# MODULIQ_CFD.net
KiCad netlist of a schematic drawn in Altium Designer
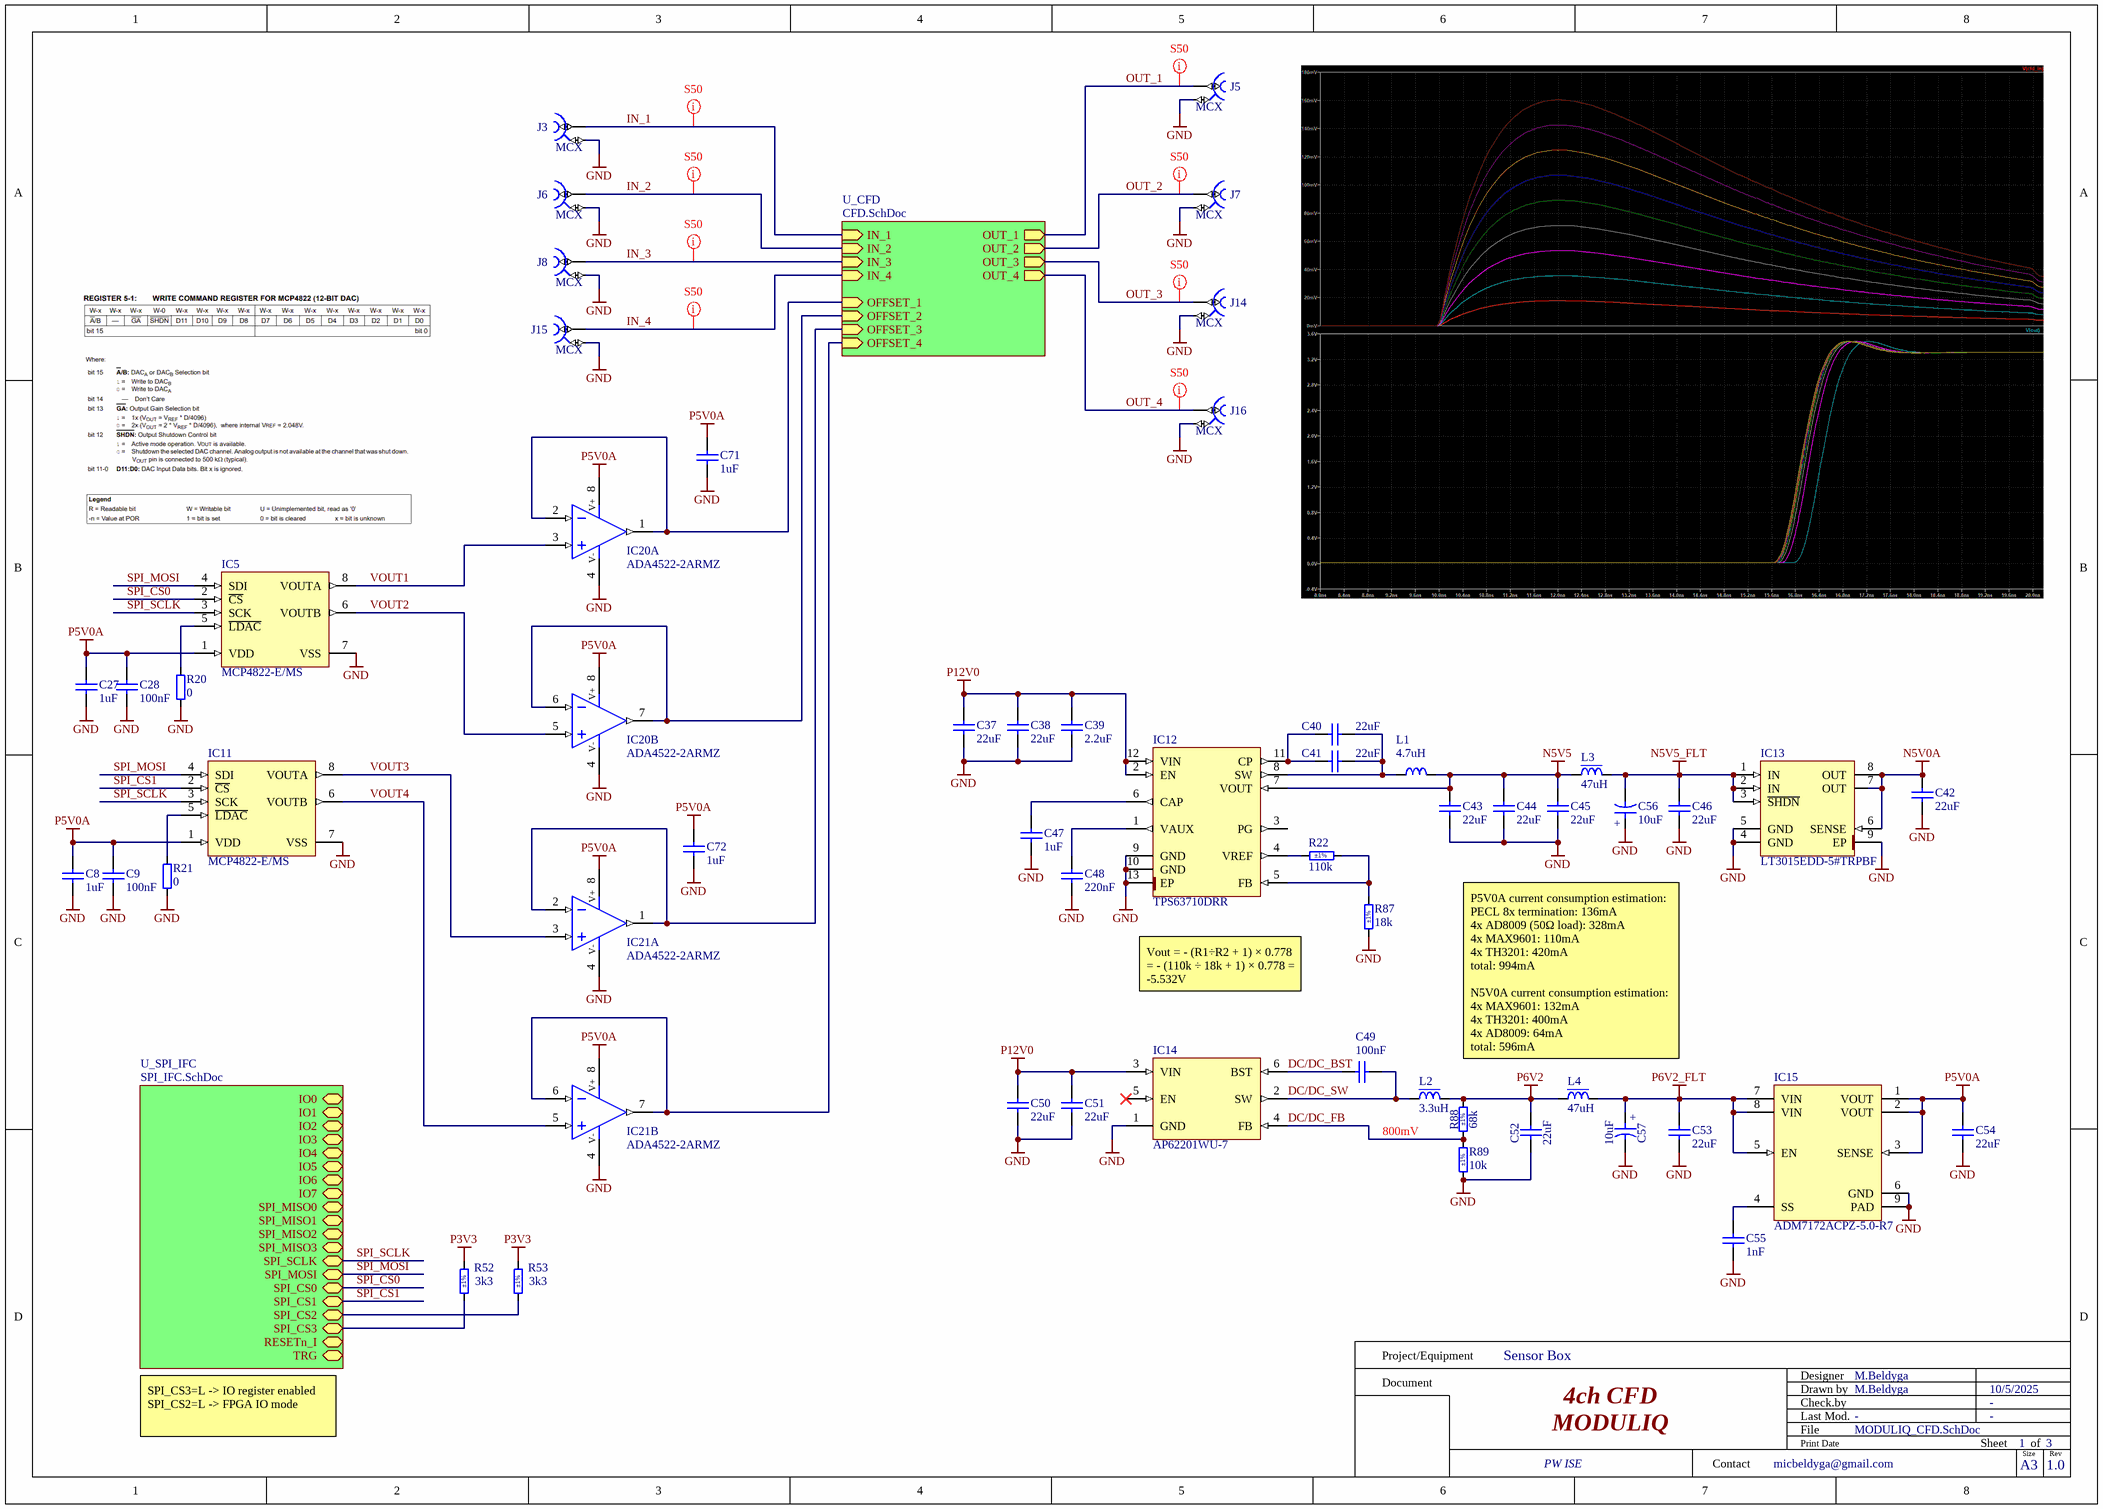
[diagram p0: MODULIQ_CFD.SchDoc]

(export (version "E")
  (design (tool "Eeschema 10.0.6"))
  (components
    (comp (ref "C8")
      (value "1uF")
      (footprint "CAPC1005X55N")
      (description "Non-polarised capacitor")
      (fields
        (field (name "PART NUMBER") "CC0402_1UF_16V_10%_X5R")
        (field (name "VOLTAGE") "16V")
        (field (name "AUTHOR") "CERN DEM JLC")
      )
      (libsource (lib "Capacitors") (part "Capacitor - non polarized"))
    )
    (comp (ref "C9")
      (value "100nF")
      (footprint "CAPC1005X55N")
      (description "Non-polarised capacitor")
      (fields
        (field (name "PART NUMBER") "CC0402_100NF_50V_10%_X7R")
        (field (name "VOLTAGE") "50V")
        (field (name "AUTHOR") "CERN DEM MR")
      )
      (libsource (lib "Capacitors") (part "Capacitor - non polarized"))
    )
    (comp (ref "C27")
      (value "1uF")
      (footprint "CAPC1005X55N")
      (description "Non-polarised capacitor")
      (fields
        (field (name "PART NUMBER") "CC0402_1UF_16V_10%_X5R")
        (field (name "VOLTAGE") "16V")
        (field (name "AUTHOR") "CERN DEM JLC")
      )
      (libsource (lib "Capacitors") (part "Capacitor - non polarized"))
    )
    (comp (ref "C28")
      (value "100nF")
      (footprint "CAPC1005X55N")
      (description "Non-polarised capacitor")
      (fields
        (field (name "PART NUMBER") "CC0402_100NF_50V_10%_X7R")
        (field (name "VOLTAGE") "50V")
        (field (name "AUTHOR") "CERN DEM MR")
      )
      (libsource (lib "Capacitors") (part "Capacitor - non polarized"))
    )
    (comp (ref "C37")
      (value "22uF")
      (footprint "CAPC2012X135N")
      (description "Non-polarised capacitor")
      (fields
        (field (name "PART NUMBER") "CC0805_22UF_16V_10%_X5R")
        (field (name "VOLTAGE") "16V")
        (field (name "AUTHOR") "CERN DEM JLC")
      )
      (libsource (lib "Capacitors") (part "Capacitor - non polarized"))
    )
    (comp (ref "C38")
      (value "22uF")
      (footprint "CAPC2012X135N")
      (description "Non-polarised capacitor")
      (fields
        (field (name "PART NUMBER") "CC0805_22UF_16V_10%_X5R")
        (field (name "VOLTAGE") "16V")
        (field (name "AUTHOR") "CERN DEM JLC")
      )
      (libsource (lib "Capacitors") (part "Capacitor - non polarized"))
    )
    (comp (ref "C39")
      (value "2.2uF")
      (footprint "CAPC1005X55N")
      (description "Non-polarised capacitor")
      (fields
        (field (name "PART NUMBER") "CC0402_2.2UF_25V_10%_X5R")
        (field (name "VOLTAGE") "25V")
        (field (name "AUTHOR") "CERN DEM BC")
      )
      (libsource (lib "Capacitors") (part "Capacitor - non polarized"))
    )
    (comp (ref "C40")
      (value "22uF")
      (footprint "CAPC2012X135N")
      (description "Non-polarised capacitor")
      (fields
        (field (name "PART NUMBER") "CC0805_22UF_16V_10%_X5R")
        (field (name "VOLTAGE") "16V")
        (field (name "AUTHOR") "CERN DEM JLC")
      )
      (libsource (lib "Capacitors") (part "Capacitor - non polarized"))
    )
    (comp (ref "C41")
      (value "22uF")
      (footprint "CAPC2012X135N")
      (description "Non-polarised capacitor")
      (fields
        (field (name "PART NUMBER") "CC0805_22UF_16V_10%_X5R")
        (field (name "VOLTAGE") "16V")
        (field (name "AUTHOR") "CERN DEM JLC")
      )
      (libsource (lib "Capacitors") (part "Capacitor - non polarized"))
    )
    (comp (ref "C42")
      (value "22uF")
      (footprint "CAPC2012X135N")
      (description "Non-polarised capacitor")
      (fields
        (field (name "PART NUMBER") "CC0805_22UF_16V_10%_X5R")
        (field (name "VOLTAGE") "16V")
        (field (name "AUTHOR") "CERN DEM JLC")
      )
      (libsource (lib "Capacitors") (part "Capacitor - non polarized"))
    )
    (comp (ref "C43")
      (value "22uF")
      (footprint "CAPC2012X135N")
      (description "Non-polarised capacitor")
      (fields
        (field (name "PART NUMBER") "CC0805_22UF_16V_10%_X5R")
        (field (name "VOLTAGE") "16V")
        (field (name "AUTHOR") "CERN DEM JLC")
      )
      (libsource (lib "Capacitors") (part "Capacitor - non polarized"))
    )
    (comp (ref "C44")
      (value "22uF")
      (footprint "CAPC2012X135N")
      (description "Non-polarised capacitor")
      (fields
        (field (name "PART NUMBER") "CC0805_22UF_16V_10%_X5R")
        (field (name "VOLTAGE") "16V")
        (field (name "AUTHOR") "CERN DEM JLC")
      )
      (libsource (lib "Capacitors") (part "Capacitor - non polarized"))
    )
    (comp (ref "C45")
      (value "22uF")
      (footprint "CAPC2012X135N")
      (description "Non-polarised capacitor")
      (fields
        (field (name "PART NUMBER") "CC0805_22UF_16V_10%_X5R")
        (field (name "VOLTAGE") "16V")
        (field (name "AUTHOR") "CERN DEM JLC")
      )
      (libsource (lib "Capacitors") (part "Capacitor - non polarized"))
    )
    (comp (ref "C46")
      (value "22uF")
      (footprint "CAPC2012X135N")
      (description "Non-polarised capacitor")
      (fields
        (field (name "PART NUMBER") "CC0805_22UF_16V_10%_X5R")
        (field (name "VOLTAGE") "16V")
        (field (name "AUTHOR") "CERN DEM JLC")
      )
      (libsource (lib "Capacitors") (part "Capacitor - non polarized"))
    )
    (comp (ref "C47")
      (value "1uF")
      (footprint "CAPC1005X55N")
      (description "Non-polarised capacitor")
      (fields
        (field (name "PART NUMBER") "CC0402_1UF_16V_10%_X5R")
        (field (name "VOLTAGE") "16V")
        (field (name "AUTHOR") "CERN DEM JLC")
      )
      (libsource (lib "Capacitors") (part "Capacitor - non polarized"))
    )
    (comp (ref "C48")
      (value "220nF")
      (footprint "CAPC1005X55N")
      (description "Non-polarised capacitor")
      (fields
        (field (name "PART NUMBER") "CC0402_220NF_25V_10%_X7R")
        (field (name "VOLTAGE") "25V")
        (field (name "AUTHOR") "CERN DEM BC")
      )
      (libsource (lib "Capacitors") (part "Capacitor - non polarized"))
    )
    (comp (ref "C49")
      (value "100nF")
      (footprint "CAPC1005X55N")
      (description "Non-polarised capacitor")
      (fields
        (field (name "PART NUMBER") "CC0402_100NF_16V_10%_X7R")
        (field (name "VOLTAGE") "16V")
        (field (name "AUTHOR") "CERN DEM JLC")
      )
      (libsource (lib "Capacitors") (part "Capacitor - non polarized"))
    )
    (comp (ref "C50")
      (value "22uF")
      (footprint "CAPC2012X135N")
      (description "Non-polarised capacitor")
      (fields
        (field (name "PART NUMBER") "CC0805_22UF_16V_10%_X5R")
        (field (name "VOLTAGE") "16V")
        (field (name "AUTHOR") "CERN DEM JLC")
      )
      (libsource (lib "Capacitors") (part "Capacitor - non polarized"))
    )
    (comp (ref "C51")
      (value "22uF")
      (footprint "CAPC2012X135N")
      (description "Non-polarised capacitor")
      (fields
        (field (name "PART NUMBER") "CC0805_22UF_16V_10%_X5R")
        (field (name "VOLTAGE") "16V")
        (field (name "AUTHOR") "CERN DEM JLC")
      )
      (libsource (lib "Capacitors") (part "Capacitor - non polarized"))
    )
    (comp (ref "C52")
      (value "22uF")
      (footprint "CAPC2012X135N")
      (description "Non-polarised capacitor")
      (fields
        (field (name "PART NUMBER") "CC0805_22UF_16V_10%_X5R")
        (field (name "VOLTAGE") "16V")
        (field (name "AUTHOR") "CERN DEM JLC")
      )
      (libsource (lib "Capacitors") (part "Capacitor - non polarized"))
    )
    (comp (ref "C53")
      (value "22uF")
      (footprint "CAPC2012X135N")
      (description "Non-polarised capacitor")
      (fields
        (field (name "PART NUMBER") "CC0805_22UF_16V_10%_X5R")
        (field (name "VOLTAGE") "16V")
        (field (name "AUTHOR") "CERN DEM JLC")
      )
      (libsource (lib "Capacitors") (part "Capacitor - non polarized"))
    )
    (comp (ref "C54")
      (value "22uF")
      (footprint "CAPC2012X135N")
      (description "Non-polarised capacitor")
      (fields
        (field (name "PART NUMBER") "CC0805_22UF_16V_10%_X5R")
        (field (name "VOLTAGE") "16V")
        (field (name "AUTHOR") "CERN DEM JLC")
      )
      (libsource (lib "Capacitors") (part "Capacitor - non polarized"))
    )
    (comp (ref "C55")
      (value "1nF")
      (footprint "CAPC1005X55N")
      (description "Non-polarised capacitor")
      (fields
        (field (name "PART NUMBER") "CC0402_1NF_50V_10%_X7R")
        (field (name "VOLTAGE") "50V")
        (field (name "AUTHOR") "CERN DEM JLC")
      )
      (libsource (lib "Capacitors") (part "Capacitor - non polarized"))
    )
    (comp (ref "C56")
      (value "10uF")
      (footprint "CAPMP3216X180N")
      (description "Polarised capacitor")
      (fields
        (field (name "PART NUMBER") "CTE3216-18_10UF_16V_20%_AVX_TCJ")
        (field (name "VOLTAGE") "16V")
        (field (name "AUTHOR") "CERN DEM JLC")
      )
      (libsource (lib "Capacitors") (part "Capacitor - polarized"))
    )
    (comp (ref "C57")
      (value "10uF")
      (footprint "CAPMP3216X180N")
      (description "Polarised capacitor")
      (fields
        (field (name "PART NUMBER") "CTE3216-18_10UF_16V_20%_AVX_TCJ")
        (field (name "VOLTAGE") "16V")
        (field (name "AUTHOR") "CERN DEM JLC")
      )
      (libsource (lib "Capacitors") (part "Capacitor - polarized"))
    )
    (comp (ref "C71")
      (value "1uF")
      (footprint "CAPC1005X55N")
      (description "Non-polarised capacitor")
      (fields
        (field (name "PART NUMBER") "CC0402_1UF_16V_10%_X5R")
        (field (name "VOLTAGE") "16V")
        (field (name "AUTHOR") "CERN DEM JLC")
      )
      (libsource (lib "Capacitors") (part "Capacitor - non polarized"))
    )
    (comp (ref "C72")
      (value "1uF")
      (footprint "CAPC1005X55N")
      (description "Non-polarised capacitor")
      (fields
        (field (name "PART NUMBER") "CC0402_1UF_16V_10%_X5R")
        (field (name "VOLTAGE") "16V")
        (field (name "AUTHOR") "CERN DEM JLC")
      )
      (libsource (lib "Capacitors") (part "Capacitor - non polarized"))
    )
    (comp (ref "IC5")
      (value "MCP4822-E/MS")
      (footprint "SOP65P490X110-8N")
      (description "12-Bit Dual Voltage Output Digital-to-Analog Converter with Internal VREF and SPI Interface")
      (fields (field (name "MANUFACTURER") "MICROCHIP TECHNOLOGY") (field (name "AUTHOR") "CERN DEM MR"))
      (libsource (lib "ICs And Semiconductors") (part "MCP4822"))
    )
    (comp (ref "IC11")
      (value "MCP4822-E/MS")
      (footprint "SOP65P490X110-8N")
      (description "12-Bit Dual Voltage Output Digital-to-Analog Converter with Internal VREF and SPI Interface")
      (fields (field (name "MANUFACTURER") "MICROCHIP TECHNOLOGY") (field (name "AUTHOR") "CERN DEM MR"))
      (libsource (lib "ICs And Semiconductors") (part "MCP4822"))
    )
    (comp (ref "IC12")
      (value "TPS63710DRR")
      (footprint "SON50P300X300X80-13N-R160X260")
      (description "-1 to -5.5VDC, 1A Output, Low Noise Synchronous Inverting Buck Converter")
      (fields (field (name "MANUFACTURER") "TEXAS INSTRUMENTS") (field (name "AUTHOR") "CERN DEM BC"))
      (libsource (lib "ICs And Semiconductors") (part "TPS63710"))
    )
    (comp (ref "IC13")
      (value "LT3015EDD-5#TRPBF")
      (footprint "SON50P300X300X80-9N-R175X248")
      (description "SP-LINREG -5V 1.5A, Low Noise, Negative Linear Regulator with Precision Current Limit")
      (fields (field (name "MANUFACTURER") "Analog Devices"))
      (libsource (lib "mb") (part "LT3015EDD-5#TRPBF"))
    )
    (comp (ref "IC14")
      (value "AP62201WU-7")
      (footprint "SOT95P280X100-6N")
      (description "4.2V TO 18V INPUT, 2A LOW IQ SYNCHRONOUS BUCK CONVERTER")
      (fields
        (field (name "MANUFACTURER") "DIODES INCORPORATED")
        (field (name "MANUFACTURER PART NUMBER") "AP62201WU")
        (field (name "AUTHOR") "CERN DEM HF")
      )
      (libsource (lib "ICs And Semiconductors") (part "AP62201WU"))
    )
    (comp (ref "IC15")
      (value "ADM7172ACPZ-5.0-R7")
      (footprint "SON50P300X80_HS-9N")
      (description "LDO Regulator Pos 5V 2A Medical 8-Pin LFCSP EP T/R")
      (fields (field (name "MANUFACTURER") "Analog Devices"))
      (libsource (lib "mb") (part "ADM7172ACPZ-5.0-R7"))
    )
    (comp (ref "IC20")
      (value "ADA4522-2ARMZ")
      (footprint "SOP65P490X110-8N")
      (description "Dual Operational Amplifier")
      (fields
        (field (name "MANUFACTURER") "ANALOG DEVICES")
        (field (name "MANUFACTURER PART NUMBER") "ADA4522-2ARM")
        (field (name "AUTHOR") "CERN DEM BC")
      )
      (libsource (lib "ICs And Semiconductors") (part "Operational Amplifier x2 Type1"))
    )
    (comp (ref "IC21")
      (value "ADA4522-2ARMZ")
      (footprint "SOP65P490X110-8N")
      (description "Dual Operational Amplifier")
      (fields
        (field (name "MANUFACTURER") "ANALOG DEVICES")
        (field (name "MANUFACTURER PART NUMBER") "ADA4522-2ARM")
        (field (name "AUTHOR") "CERN DEM BC")
      )
      (libsource (lib "ICs And Semiconductors") (part "Operational Amplifier x2 Type1"))
    )
    (comp (ref "J3")
      (value "MCX")
      (footprint "AMPHENOL_919-109J-51PX")
      (fields
        (field (name "PART NUMBER") "AMPHENOL_919-109J-51PX")
        (field (name "MANUFACTURER") "AMPHENOL")
        (field (name "MANUFACTURER PART NUMBER") "919-109J-51PX (MCX6251B1-3GT30G-50)")
        (field (name "AUTHOR") "CERN DEM BC")
      )
      (libsource (lib "") (part "Coax_1Female_1Shield_1"))
    )
    (comp (ref "J5")
      (value "MCX")
      (footprint "AMPHENOL_919-109J-51PX")
      (fields
        (field (name "PART NUMBER") "AMPHENOL_919-109J-51PX")
        (field (name "MANUFACTURER") "AMPHENOL")
        (field (name "MANUFACTURER PART NUMBER") "919-109J-51PX (MCX6251B1-3GT30G-50)")
        (field (name "AUTHOR") "CERN DEM BC")
      )
      (libsource (lib "Connectors") (part "Coax_1Female_1Shield"))
    )
    (comp (ref "J6")
      (value "MCX")
      (footprint "AMPHENOL_919-109J-51PX")
      (fields
        (field (name "PART NUMBER") "AMPHENOL_919-109J-51PX")
        (field (name "MANUFACTURER") "AMPHENOL")
        (field (name "MANUFACTURER PART NUMBER") "919-109J-51PX (MCX6251B1-3GT30G-50)")
        (field (name "AUTHOR") "CERN DEM BC")
      )
      (libsource (lib "") (part "Coax_1Female_1Shield_1"))
    )
    (comp (ref "J7")
      (value "MCX")
      (footprint "AMPHENOL_919-109J-51PX")
      (fields
        (field (name "PART NUMBER") "AMPHENOL_919-109J-51PX")
        (field (name "MANUFACTURER") "AMPHENOL")
        (field (name "MANUFACTURER PART NUMBER") "919-109J-51PX (MCX6251B1-3GT30G-50)")
        (field (name "AUTHOR") "CERN DEM BC")
      )
      (libsource (lib "Connectors") (part "Coax_1Female_1Shield"))
    )
    (comp (ref "J8")
      (value "MCX")
      (footprint "AMPHENOL_919-109J-51PX")
      (fields
        (field (name "PART NUMBER") "AMPHENOL_919-109J-51PX")
        (field (name "MANUFACTURER") "AMPHENOL")
        (field (name "MANUFACTURER PART NUMBER") "919-109J-51PX (MCX6251B1-3GT30G-50)")
        (field (name "AUTHOR") "CERN DEM BC")
      )
      (libsource (lib "") (part "Coax_1Female_1Shield_1"))
    )
    (comp (ref "J14")
      (value "MCX")
      (footprint "AMPHENOL_919-109J-51PX")
      (fields
        (field (name "PART NUMBER") "AMPHENOL_919-109J-51PX")
        (field (name "MANUFACTURER") "AMPHENOL")
        (field (name "MANUFACTURER PART NUMBER") "919-109J-51PX (MCX6251B1-3GT30G-50)")
        (field (name "AUTHOR") "CERN DEM BC")
      )
      (libsource (lib "Connectors") (part "Coax_1Female_1Shield"))
    )
    (comp (ref "J15")
      (value "MCX")
      (footprint "AMPHENOL_919-109J-51PX")
      (fields
        (field (name "PART NUMBER") "AMPHENOL_919-109J-51PX")
        (field (name "MANUFACTURER") "AMPHENOL")
        (field (name "MANUFACTURER PART NUMBER") "919-109J-51PX (MCX6251B1-3GT30G-50)")
        (field (name "AUTHOR") "CERN DEM BC")
      )
      (libsource (lib "") (part "Coax_1Female_1Shield_1"))
    )
    (comp (ref "J16")
      (value "MCX")
      (footprint "AMPHENOL_919-109J-51PX")
      (fields
        (field (name "PART NUMBER") "AMPHENOL_919-109J-51PX")
        (field (name "MANUFACTURER") "AMPHENOL")
        (field (name "MANUFACTURER PART NUMBER") "919-109J-51PX (MCX6251B1-3GT30G-50)")
        (field (name "AUTHOR") "CERN DEM BC")
      )
      (libsource (lib "Connectors") (part "Coax_1Female_1Shield"))
    )
    (comp (ref "L1")
      (value "4.7uH")
      (footprint "IND_COILCRAFT_EPL3015")
      (description "Inductor")
      (fields
        (field (name "PART NUMBER") "IND_4.7UH_20%_COILCRAFT_EPL3015")
        (field (name "POWER") "1A")
        (field (name "AUTHOR") "CERN DEM BC")
      )
      (libsource (lib "Inductors & Transformers") (part "Inductor"))
    )
    (comp (ref "L2")
      (value "3.3uH")
      (footprint "IND_COILCRAFT_SD43")
      (description "Inductor With Core")
      (fields
        (field (name "PART NUMBER") "IND_3.3UH_20%_COILCRAFT_SD43-332MLB")
        (field (name "POWER") "2.1A")
        (field (name "AUTHOR") "CERN DEM JLC")
      )
      (libsource (lib "Inductors & Transformers") (part "Inductor With Magnetic core"))
    )
    (comp (ref "L3")
      (value "47uH")
      (footprint "IND_WURTH_WE-LHMI_7050")
      (description "Inductor With Core")
      (fields
        (field (name "PART NUMBER") "IND_47UH_20%_WURTH_WE-LHMI_74437349470")
        (field (name "POWER") "1.45A")
        (field (name "AUTHOR") "CERN DEM HF")
      )
      (libsource (lib "Inductors & Transformers") (part "Inductor With Magnetic core"))
    )
    (comp (ref "L4")
      (value "47uH")
      (footprint "IND_WURTH_WE-LHMI_7050")
      (description "Inductor With Core")
      (fields
        (field (name "PART NUMBER") "IND_47UH_20%_WURTH_WE-LHMI_74437349470")
        (field (name "POWER") "1.45A")
        (field (name "AUTHOR") "CERN DEM HF")
      )
      (libsource (lib "Inductors & Transformers") (part "Inductor With Magnetic core"))
    )
    (comp (ref "R20")
      (value "0")
      (footprint "RESC1005X40N")
      (description "Resistor")
      (fields
        (field (name "PART NUMBER") "R0402_0R_JUMPER")
        (field (name "MANUFACTURER") "GENERIC")
        (field (name "AUTHOR") "CERN DEM JLC")
      )
      (libsource (lib "Resistors") (part "Resistor"))
    )
    (comp (ref "R21")
      (value "0")
      (footprint "RESC1005X40N")
      (description "Resistor")
      (fields
        (field (name "PART NUMBER") "R0402_0R_JUMPER")
        (field (name "MANUFACTURER") "GENERIC")
        (field (name "AUTHOR") "CERN DEM JLC")
      )
      (libsource (lib "Resistors") (part "Resistor"))
    )
    (comp (ref "R22")
      (value "110k")
      (footprint "RESC1005X40N")
      (description "Resistor - 1%")
      (fields
        (field (name "TOLERANCE") "±1%")
        (field (name "PART NUMBER") "R0402_110K_1%_0.0625W_100PPM")
        (field (name "POWER") "0.0625W")
        (field (name "AUTHOR") "CERN DEM JLC")
      )
      (libsource (lib "Resistors") (part "Resistor - 1%"))
    )
    (comp (ref "R52")
      (value "3k3")
      (footprint "RESC1005X40N")
      (description "Resistor - 1%")
      (fields
        (field (name "TOLERANCE") "±1%")
        (field (name "PART NUMBER") "R0402_3K3_1%_0.0625W_100PPM")
        (field (name "POWER") "0.0625W")
        (field (name "AUTHOR") "CERN DEM JLC")
      )
      (libsource (lib "Resistors") (part "Resistor - 1%"))
    )
    (comp (ref "R53")
      (value "3k3")
      (footprint "RESC1005X40N")
      (description "Resistor - 1%")
      (fields
        (field (name "TOLERANCE") "±1%")
        (field (name "PART NUMBER") "R0402_3K3_1%_0.0625W_100PPM")
        (field (name "POWER") "0.0625W")
        (field (name "AUTHOR") "CERN DEM JLC")
      )
      (libsource (lib "Resistors") (part "Resistor - 1%"))
    )
    (comp (ref "R87")
      (value "18k")
      (footprint "RESC1005X40N")
      (description "Resistor - 1%")
      (fields
        (field (name "TOLERANCE") "±1%")
        (field (name "PART NUMBER") "R0402_18K_1%_0.0625W_100PPM")
        (field (name "POWER") "0.0625W")
        (field (name "AUTHOR") "CERN DEM JLC")
      )
      (libsource (lib "Resistors") (part "Resistor - 1%"))
    )
    (comp (ref "R88")
      (value "68k")
      (footprint "RESC1005X40N")
      (description "Resistor - 1%")
      (fields
        (field (name "TOLERANCE") "±1%")
        (field (name "PART NUMBER") "R0402_68K_1%_0.0625W_100PPM")
        (field (name "POWER") "0.0625W")
        (field (name "AUTHOR") "CERN DEM JLC")
      )
      (libsource (lib "Resistors") (part "Resistor - 1%"))
    )
    (comp (ref "R89")
      (value "10k")
      (footprint "RESC1005X40N")
      (description "Resistor - 1%")
      (fields
        (field (name "TOLERANCE") "±1%")
        (field (name "PART NUMBER") "R0402_10K_1%_0.0625W_100PPM")
        (field (name "POWER") "0.0625W")
        (field (name "AUTHOR") "CERN DEM JLC")
      )
      (libsource (lib "Resistors") (part "Resistor - 1%"))
    )
  )
  (nets
    (net (code "1") (name "/DC{slash}DC_BST") (class "Default")
      (node (ref "C49") (pin "1") (pinfunction "1_1") (pintype "passive"))
      (node (ref "IC14") (pin "6") (pinfunction "BST_6") (pintype "input"))
    )
    (net (code "2") (name "/DC{slash}DC_FB") (class "Default")
      (node (ref "IC14") (pin "4") (pinfunction "FB_4") (pintype "input"))
      (node (ref "R88") (pin "1") (pinfunction "1_1") (pintype "passive"))
      (node (ref "R89") (pin "2") (pinfunction "2_2") (pintype "passive"))
    )
    (net (code "3") (name "/DC{slash}DC_SW") (class "Default")
      (node (ref "C49") (pin "2") (pinfunction "2_2") (pintype "passive"))
      (node (ref "IC14") (pin "2") (pinfunction "SW_2") (pintype "output"))
      (node (ref "L2") (pin "1") (pinfunction "1_1") (pintype "passive"))
    )
    (net (code "4") (name "/IN_1") (class "Default")
      (node (ref "J3") (pin "1") (pinfunction "1_1") (pintype "bidirectional"))
    )
    (net (code "5") (name "/IN_2") (class "Default")
      (node (ref "J6") (pin "1") (pinfunction "1_1") (pintype "bidirectional"))
    )
    (net (code "6") (name "/IN_3") (class "Default")
      (node (ref "J8") (pin "1") (pinfunction "1_1") (pintype "bidirectional"))
    )
    (net (code "7") (name "/IN_4") (class "Default")
      (node (ref "J15") (pin "1") (pinfunction "1_1") (pintype "bidirectional"))
    )
    (net (code "16") (name "/OFFSET_1") (class "Default")
      (node (ref "IC20") (pin "1") (pinfunction "OUT_1") (pintype "output"))
      (node (ref "IC20") (pin "2") (pinfunction "IN-_2") (pintype "input"))
    )
    (net (code "17") (name "/OFFSET_2") (class "Default")
      (node (ref "IC20") (pin "6") (pinfunction "IN-_6") (pintype "input"))
      (node (ref "IC20") (pin "7") (pinfunction "OUT_7") (pintype "output"))
    )
    (net (code "18") (name "/OFFSET_3") (class "Default")
      (node (ref "IC21") (pin "1") (pinfunction "OUT_1") (pintype "output"))
      (node (ref "IC21") (pin "2") (pinfunction "IN-_2") (pintype "input"))
    )
    (net (code "19") (name "/OFFSET_4") (class "Default")
      (node (ref "IC21") (pin "6") (pinfunction "IN-_6") (pintype "input"))
      (node (ref "IC21") (pin "7") (pinfunction "OUT_7") (pintype "output"))
    )
    (net (code "20") (name "/OUT_1") (class "Default")
      (node (ref "J5") (pin "1") (pinfunction "1_1") (pintype "bidirectional"))
    )
    (net (code "21") (name "/OUT_2") (class "Default")
      (node (ref "J7") (pin "1") (pinfunction "1_1") (pintype "bidirectional"))
    )
    (net (code "22") (name "/OUT_3") (class "Default")
      (node (ref "J14") (pin "1") (pinfunction "1_1") (pintype "bidirectional"))
    )
    (net (code "23") (name "/OUT_4") (class "Default")
      (node (ref "J16") (pin "1") (pinfunction "1_1") (pintype "bidirectional"))
    )
    (net (code "25") (name "/SPI_CS0") (class "Default")
      (node (ref "IC5") (pin "2") (pinfunction "~{CS}_2") (pintype "input"))
    )
    (net (code "26") (name "/SPI_CS1") (class "Default")
      (node (ref "IC11") (pin "2") (pinfunction "~{CS}_2") (pintype "input"))
    )
    (net (code "27") (name "/SPI_CS2") (class "Default")
      (node (ref "R53") (pin "2") (pinfunction "2_2") (pintype "passive"))
    )
    (net (code "28") (name "/SPI_CS3") (class "Default")
      (node (ref "R52") (pin "2") (pinfunction "2_2") (pintype "passive"))
    )
    (net (code "33") (name "/SPI_MOSI") (class "Default")
      (node (ref "IC11") (pin "4") (pinfunction "SDI_4") (pintype "input"))
      (node (ref "IC5") (pin "4") (pinfunction "SDI_4") (pintype "input"))
    )
    (net (code "34") (name "/SPI_SCLK") (class "Default")
      (node (ref "IC11") (pin "3") (pinfunction "SCK_3") (pintype "input"))
      (node (ref "IC5") (pin "3") (pinfunction "SCK_3") (pintype "input"))
    )
    (net (code "36") (name "/VOUT1") (class "Default")
      (node (ref "IC20") (pin "3") (pinfunction "IN+_3") (pintype "input"))
      (node (ref "IC5") (pin "8") (pinfunction "VOUTA_8") (pintype "output"))
    )
    (net (code "37") (name "/VOUT2") (class "Default")
      (node (ref "IC20") (pin "5") (pinfunction "IN+_5") (pintype "input"))
      (node (ref "IC5") (pin "6") (pinfunction "VOUTB_6") (pintype "output"))
    )
    (net (code "38") (name "/VOUT3") (class "Default")
      (node (ref "IC11") (pin "8") (pinfunction "VOUTA_8") (pintype "output"))
      (node (ref "IC21") (pin "3") (pinfunction "IN+_3") (pintype "input"))
    )
    (net (code "39") (name "/VOUT4") (class "Default")
      (node (ref "IC11") (pin "6") (pinfunction "VOUTB_6") (pintype "output"))
      (node (ref "IC21") (pin "5") (pinfunction "IN+_5") (pintype "input"))
    )
    (net (code "40") (name "GND") (class "Default")
      (node (ref "C27") (pin "1") (pinfunction "1_1") (pintype "passive"))
      (node (ref "C28") (pin "1") (pinfunction "1_1") (pintype "passive"))
      (node (ref "C37") (pin "1") (pinfunction "1_1") (pintype "passive"))
      (node (ref "C38") (pin "1") (pinfunction "1_1") (pintype "passive"))
      (node (ref "C39") (pin "1") (pinfunction "1_1") (pintype "passive"))
      (node (ref "C42") (pin "1") (pinfunction "1_1") (pintype "passive"))
      (node (ref "C43") (pin "1") (pinfunction "1_1") (pintype "passive"))
      (node (ref "C44") (pin "1") (pinfunction "1_1") (pintype "passive"))
      (node (ref "C45") (pin "1") (pinfunction "1_1") (pintype "passive"))
      (node (ref "C46") (pin "1") (pinfunction "1_1") (pintype "passive"))
      (node (ref "C47") (pin "1") (pinfunction "1_1") (pintype "passive"))
      (node (ref "C48") (pin "1") (pinfunction "1_1") (pintype "passive"))
      (node (ref "C50") (pin "1") (pinfunction "1_1") (pintype "passive"))
      (node (ref "C51") (pin "1") (pinfunction "1_1") (pintype "passive"))
      (node (ref "C52") (pin "1") (pinfunction "1_1") (pintype "passive"))
      (node (ref "C53") (pin "1") (pinfunction "1_1") (pintype "passive"))
      (node (ref "C54") (pin "1") (pinfunction "1_1") (pintype "passive"))
      (node (ref "C55") (pin "1") (pinfunction "1_1") (pintype "passive"))
      (node (ref "C56") (pin "1") (pinfunction "1_1") (pintype "passive"))
      (node (ref "C57") (pin "2") (pinfunction "2_2") (pintype "passive"))
      (node (ref "C71") (pin "1") (pinfunction "1_1") (pintype "passive"))
      (node (ref "C72") (pin "1") (pinfunction "1_1") (pintype "passive"))
      (node (ref "C8") (pin "1") (pinfunction "1_1") (pintype "passive"))
      (node (ref "C9") (pin "1") (pinfunction "1_1") (pintype "passive"))
      (node (ref "IC11") (pin "7") (pinfunction "VSS_7") (pintype "power_in"))
      (node (ref "IC12") (pin "10") (pinfunction "GND_10") (pintype "power_in"))
      (node (ref "IC12") (pin "13") (pinfunction "EP_13") (pintype "power_in"))
      (node (ref "IC12") (pin "9") (pinfunction "GND_9") (pintype "power_in"))
      (node (ref "IC13") (pin "4") (pinfunction "GND_4") (pintype "power_in"))
      (node (ref "IC13") (pin "5") (pinfunction "GND_5") (pintype "power_in"))
      (node (ref "IC13") (pin "9") (pinfunction "EP_9") (pintype "power_in"))
      (node (ref "IC14") (pin "1") (pinfunction "GND_1") (pintype "power_in"))
      (node (ref "IC15") (pin "6") (pinfunction "GND_6") (pintype "power_in"))
      (node (ref "IC15") (pin "9") (pinfunction "PAD_9") (pintype "power_in"))
      (node (ref "IC20") (pin "4") (pinfunction "V-_4") (pintype "power_in"))
      (node (ref "IC21") (pin "4") (pinfunction "V-_4") (pintype "power_in"))
      (node (ref "IC5") (pin "7") (pinfunction "VSS_7") (pintype "power_in"))
      (node (ref "J14") (pin "2") (pinfunction "2_2") (pintype "bidirectional"))
      (node (ref "J15") (pin "2") (pinfunction "2_2") (pintype "bidirectional"))
      (node (ref "J16") (pin "2") (pinfunction "2_2") (pintype "bidirectional"))
      (node (ref "J3") (pin "2") (pinfunction "2_2") (pintype "bidirectional"))
      (node (ref "J5") (pin "2") (pinfunction "2_2") (pintype "bidirectional"))
      (node (ref "J6") (pin "2") (pinfunction "2_2") (pintype "bidirectional"))
      (node (ref "J7") (pin "2") (pinfunction "2_2") (pintype "bidirectional"))
      (node (ref "J8") (pin "2") (pinfunction "2_2") (pintype "bidirectional"))
      (node (ref "R20") (pin "1") (pinfunction "1_1") (pintype "passive"))
      (node (ref "R21") (pin "1") (pinfunction "1_1") (pintype "passive"))
      (node (ref "R87") (pin "1") (pinfunction "1_1") (pintype "passive"))
      (node (ref "R89") (pin "1") (pinfunction "1_1") (pintype "passive"))
    )
    (net (code "41") (name "N5V0A") (class "Default")
      (node (ref "C42") (pin "2") (pinfunction "2_2") (pintype "passive"))
      (node (ref "IC13") (pin "6") (pinfunction "SENSE_6") (pintype "input"))
      (node (ref "IC13") (pin "7") (pinfunction "OUT_7") (pintype "power_in"))
      (node (ref "IC13") (pin "8") (pinfunction "OUT_8") (pintype "power_in"))
    )
    (net (code "42") (name "N5V5") (class "Default")
      (node (ref "C43") (pin "2") (pinfunction "2_2") (pintype "passive"))
      (node (ref "C44") (pin "2") (pinfunction "2_2") (pintype "passive"))
      (node (ref "C45") (pin "2") (pinfunction "2_2") (pintype "passive"))
      (node (ref "IC12") (pin "7") (pinfunction "VOUT_7") (pintype "input"))
      (node (ref "L1") (pin "2") (pinfunction "2_2") (pintype "passive"))
      (node (ref "L3") (pin "1") (pinfunction "1_1") (pintype "passive"))
    )
    (net (code "43") (name "N5V5_FLT") (class "Default")
      (node (ref "C46") (pin "2") (pinfunction "2_2") (pintype "passive"))
      (node (ref "C56") (pin "2") (pinfunction "2_2") (pintype "passive"))
      (node (ref "IC13") (pin "1") (pinfunction "IN_1") (pintype "input"))
      (node (ref "IC13") (pin "2") (pinfunction "IN_2") (pintype "input"))
      (node (ref "IC13") (pin "3") (pinfunction "~{SHDN}_3") (pintype "input"))
      (node (ref "L3") (pin "2") (pinfunction "2_2") (pintype "passive"))
    )
    (net (code "44") (name "Net-(IC5-~{LDAC})") (class "Default")
      (node (ref "IC5") (pin "5") (pinfunction "~{LDAC}_5") (pintype "input"))
      (node (ref "R20") (pin "2") (pinfunction "2_2") (pintype "passive"))
    )
    (net (code "45") (name "Net-(IC11-~{LDAC})") (class "Default")
      (node (ref "IC11") (pin "5") (pinfunction "~{LDAC}_5") (pintype "input"))
      (node (ref "R21") (pin "2") (pinfunction "2_2") (pintype "passive"))
    )
    (net (code "46") (name "Net-(IC12-CAP)") (class "Default")
      (node (ref "C47") (pin "2") (pinfunction "2_2") (pintype "passive"))
      (node (ref "IC12") (pin "6") (pinfunction "CAP_6") (pintype "output"))
    )
    (net (code "47") (name "Net-(IC12-CP)") (class "Default")
      (node (ref "C40") (pin "2") (pinfunction "2_2") (pintype "passive"))
      (node (ref "C41") (pin "2") (pinfunction "2_2") (pintype "passive"))
      (node (ref "IC12") (pin "11") (pinfunction "CP_11") (pintype "output"))
    )
    (net (code "48") (name "Net-(IC12-FB)") (class "Default")
      (node (ref "IC12") (pin "5") (pinfunction "FB_5") (pintype "input"))
      (node (ref "R22") (pin "2") (pinfunction "2_2") (pintype "passive"))
      (node (ref "R87") (pin "2") (pinfunction "2_2") (pintype "passive"))
    )
    (net (code "49") (name "Net-(IC12-SW)") (class "Default")
      (node (ref "C40") (pin "1") (pinfunction "1_1") (pintype "passive"))
      (node (ref "C41") (pin "1") (pinfunction "1_1") (pintype "passive"))
      (node (ref "IC12") (pin "8") (pinfunction "SW_8") (pintype "output"))
      (node (ref "L1") (pin "1") (pinfunction "1_1") (pintype "passive"))
    )
    (net (code "50") (name "Net-(IC12-VAUX)") (class "Default")
      (node (ref "C48") (pin "2") (pinfunction "2_2") (pintype "passive"))
      (node (ref "IC12") (pin "1") (pinfunction "VAUX_1") (pintype "output"))
    )
    (net (code "51") (name "Net-(IC12-VREF)") (class "Default")
      (node (ref "IC12") (pin "4") (pinfunction "VREF_4") (pintype "output"))
      (node (ref "R22") (pin "1") (pinfunction "1_1") (pintype "passive"))
    )
    (net (code "52") (name "Net-(IC15-SS)") (class "Default")
      (node (ref "C55") (pin "2") (pinfunction "2_2") (pintype "passive"))
      (node (ref "IC15") (pin "4") (pinfunction "SS_4") (pintype "passive"))
    )
    (net (code "53") (name "P3V3") (class "Default")
      (node (ref "R52") (pin "1") (pinfunction "1_1") (pintype "passive"))
      (node (ref "R53") (pin "1") (pinfunction "1_1") (pintype "passive"))
    )
    (net (code "54") (name "P5V0A") (class "Default")
      (node (ref "C27") (pin "2") (pinfunction "2_2") (pintype "passive"))
      (node (ref "C28") (pin "2") (pinfunction "2_2") (pintype "passive"))
      (node (ref "C54") (pin "2") (pinfunction "2_2") (pintype "passive"))
      (node (ref "C71") (pin "2") (pinfunction "2_2") (pintype "passive"))
      (node (ref "C72") (pin "2") (pinfunction "2_2") (pintype "passive"))
      (node (ref "C8") (pin "2") (pinfunction "2_2") (pintype "passive"))
      (node (ref "C9") (pin "2") (pinfunction "2_2") (pintype "passive"))
      (node (ref "IC11") (pin "1") (pinfunction "VDD_1") (pintype "input"))
      (node (ref "IC15") (pin "1") (pinfunction "VOUT_1") (pintype "power_in"))
      (node (ref "IC15") (pin "2") (pinfunction "VOUT_2") (pintype "power_in"))
      (node (ref "IC15") (pin "3") (pinfunction "SENSE_3") (pintype "input"))
      (node (ref "IC20") (pin "8") (pinfunction "V+_8") (pintype "power_in"))
      (node (ref "IC21") (pin "8") (pinfunction "V+_8") (pintype "power_in"))
      (node (ref "IC5") (pin "1") (pinfunction "VDD_1") (pintype "input"))
    )
    (net (code "55") (name "P6V2") (class "Default")
      (node (ref "C52") (pin "2") (pinfunction "2_2") (pintype "passive"))
      (node (ref "L2") (pin "2") (pinfunction "2_2") (pintype "passive"))
      (node (ref "L4") (pin "1") (pinfunction "1_1") (pintype "passive"))
      (node (ref "R88") (pin "2") (pinfunction "2_2") (pintype "passive"))
    )
    (net (code "56") (name "P6V2_FLT") (class "Default")
      (node (ref "C53") (pin "2") (pinfunction "2_2") (pintype "passive"))
      (node (ref "C57") (pin "1") (pinfunction "1_1") (pintype "passive"))
      (node (ref "IC15") (pin "5") (pinfunction "EN_5") (pintype "input"))
      (node (ref "IC15") (pin "7") (pinfunction "VIN_7") (pintype "power_in"))
      (node (ref "IC15") (pin "8") (pinfunction "VIN_8") (pintype "power_in"))
      (node (ref "L4") (pin "2") (pinfunction "2_2") (pintype "passive"))
    )
    (net (code "57") (name "P12V0") (class "Default")
      (node (ref "C37") (pin "2") (pinfunction "2_2") (pintype "passive"))
      (node (ref "C38") (pin "2") (pinfunction "2_2") (pintype "passive"))
      (node (ref "C39") (pin "2") (pinfunction "2_2") (pintype "passive"))
      (node (ref "C50") (pin "2") (pinfunction "2_2") (pintype "passive"))
      (node (ref "C51") (pin "2") (pinfunction "2_2") (pintype "passive"))
      (node (ref "IC12") (pin "12") (pinfunction "VIN_12") (pintype "input"))
      (node (ref "IC12") (pin "2") (pinfunction "EN_2") (pintype "input"))
      (node (ref "IC14") (pin "3") (pinfunction "VIN_3") (pintype "input"))
    )
    (net (code "58") (name "unconnected-(IC12-PG-Pad3)") (class "Default")
      (node (ref "IC12") (pin "3") (pinfunction "PG_3") (pintype "output"))
    )
    (net (code "59") (name "unconnected-(IC14-EN-Pad5)") (class "Default")
      (node (ref "IC14") (pin "5") (pinfunction "EN_5") (pintype "input+no_connect"))
    )
  )
)
